# HV_Module.net
KiCad netlist of a schematic drawn in Altium Designer
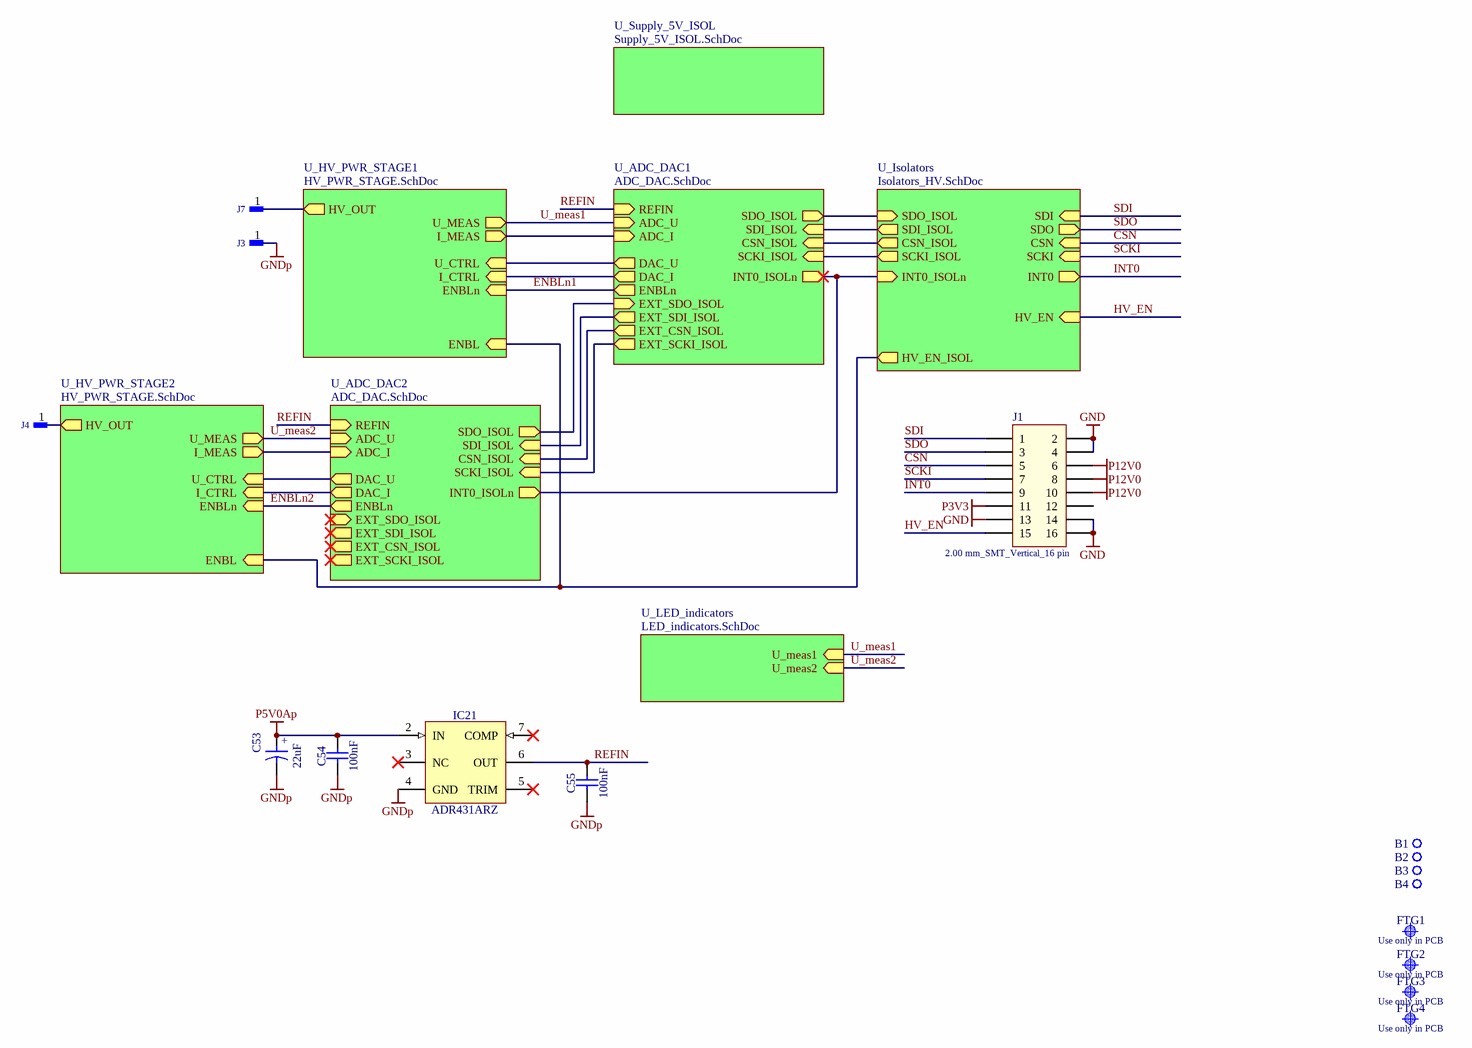
[diagram p0: HV_Module.schdoc]

(export (version "E")
  (design (tool "Eeschema 10.0.6"))
  (components
    (comp (ref "B1")
      (value "Plated Hole")
      (footprint "MTG270_500")
      (description "Single Terminal Socket")
      (fields (field (name "PART NUMBER") "PLATED_HOLE2.7_PAD5.0") (field (name "AUTHOR") "CERN DEM JMW"))
      (libsource (lib "Eletro-mechanical") (part "Single Terminal Socket"))
    )
    (comp (ref "B2")
      (value "Plated Hole")
      (footprint "MTG270_500")
      (description "Single Terminal Socket")
      (fields (field (name "PART NUMBER") "PLATED_HOLE2.7_PAD5.0") (field (name "AUTHOR") "CERN DEM JMW"))
      (libsource (lib "Eletro-mechanical") (part "Single Terminal Socket"))
    )
    (comp (ref "B3")
      (value "Plated Hole")
      (footprint "MTG270_500")
      (description "Single Terminal Socket")
      (fields (field (name "PART NUMBER") "PLATED_HOLE2.7_PAD5.0") (field (name "AUTHOR") "CERN DEM JMW"))
      (libsource (lib "Eletro-mechanical") (part "Single Terminal Socket"))
    )
    (comp (ref "B4")
      (value "Plated Hole")
      (footprint "MTG270_500")
      (description "Single Terminal Socket")
      (fields (field (name "PART NUMBER") "PLATED_HOLE2.7_PAD5.0") (field (name "AUTHOR") "CERN DEM JMW"))
      (libsource (lib "Eletro-mechanical") (part "Single Terminal Socket"))
    )
    (comp (ref "C53")
      (value "22uF")
      (footprint "CAPMP3528X210N")
      (description "Polarised capacitor")
      (fields
        (field (name "PART NUMBER") "CTE3528-21_22UF_20V_10%")
        (field (name "VOLTAGE") "20V")
        (field (name "AUTHOR") "CERN DEM JLC")
      )
      (libsource (lib "Capacitors") (part "Capacitor - polarized"))
    )
    (comp (ref "C54")
      (value "100nF")
      (footprint "CAPC1005X55N")
      (description "Non-polarised capacitor")
      (fields
        (field (name "PART NUMBER") "CC0402_100NF_16V_10%_X7R")
        (field (name "VOLTAGE") "16V")
        (field (name "AUTHOR") "CERN DEM JLC")
      )
      (libsource (lib "Capacitors") (part "Capacitor - non polarized"))
    )
    (comp (ref "C55")
      (value "100nF")
      (footprint "CAPC1005X55N")
      (description "Non-polarised capacitor")
      (fields
        (field (name "PART NUMBER") "CC0402_100NF_16V_10%_X7R")
        (field (name "VOLTAGE") "16V")
        (field (name "AUTHOR") "CERN DEM JLC")
      )
      (libsource (lib "Capacitors") (part "Capacitor - non polarized"))
    )
    (comp (ref "FTG1")
      (value "Use only in PCB")
      (footprint "FIDUCIAL_TOP_C100-200")
      (description "Fiducial Target")
      (fields (field (name "PART NUMBER") "FIDUCIAL_TARGET_C100-200") (field (name "AUTHOR") "CERN DEM JLC"))
      (libsource (lib "Eletro-mechanical") (part "Fiducial Target"))
    )
    (comp (ref "FTG2")
      (value "Use only in PCB")
      (footprint "FIDUCIAL_TOP_S100-200")
      (description "Fiducial Target")
      (fields (field (name "PART NUMBER") "FIDUCIAL_TARGET_S100-200") (field (name "AUTHOR") "CERN DEM JLC"))
      (libsource (lib "Eletro-mechanical") (part "Fiducial Target"))
    )
    (comp (ref "FTG3")
      (value "Use only in PCB")
      (footprint "FIDUCIAL_TOP_S100-200")
      (description "Fiducial Target")
      (fields (field (name "PART NUMBER") "FIDUCIAL_TARGET_S100-200") (field (name "AUTHOR") "CERN DEM JLC"))
      (libsource (lib "Eletro-mechanical") (part "Fiducial Target"))
    )
    (comp (ref "FTG4")
      (value "Use only in PCB")
      (footprint "FIDUCIAL_TOP_S100-200")
      (description "Fiducial Target")
      (fields (field (name "PART NUMBER") "FIDUCIAL_TARGET_S100-200") (field (name "AUTHOR") "CERN DEM JLC"))
      (libsource (lib "Eletro-mechanical") (part "Fiducial Target"))
    )
    (comp (ref "IC21")
      (value "ADR431ARZ")
      (footprint "SOIC127P600X175-8N")
      (fields (field (name "MANUFACTURER") "ANALOG DEVICES") (field (name "AUTHOR") "CERN DEM JLC"))
      (libsource (lib "ICs And Semiconductors") (part "ADR431"))
    )
    (comp (ref "J1")
      (value "2.00 mm_SMT_Vertical_16 pin")
      (footprint "62131621821")
      (description "Socket Header WR-PHD, Pitch 2.00 mm, SMT, Vertical, dual row, 16 pin")
      (fields (field (name "PART NUMBER") "62131621821") (field (name "PUBLISHER") "Wurth Elektronik"))
      (libsource (lib "ALTIUM-PHD_2_0_SMT_DUAL_SOCKET_HEADER_LOW_PROFILE_REEL_6213XX21821-rev18a") (part "62131621821"))
    )
    (comp (ref "J3")
      (value "SMD Pad")
      (footprint "R400X300")
      (description "Single SMD Pad")
      (fields (field (name "PART NUMBER") "SMD_PAD_4X3MM") (field (name "AUTHOR") "CERN DEM JLC"))
      (libsource (lib "Eletro-mechanical") (part "Single SMD Pad"))
    )
    (comp (ref "J4")
      (value "SMD Pad")
      (footprint "R400X300")
      (description "Single SMD Pad")
      (fields (field (name "PART NUMBER") "SMD_PAD_4X3MM") (field (name "AUTHOR") "CERN DEM JLC"))
      (libsource (lib "Eletro-mechanical") (part "Single SMD Pad"))
    )
    (comp (ref "J7")
      (value "SMD Pad")
      (footprint "R400X300")
      (description "Single SMD Pad")
      (fields (field (name "PART NUMBER") "SMD_PAD_4X3MM") (field (name "AUTHOR") "CERN DEM JLC"))
      (libsource (lib "Eletro-mechanical") (part "Single SMD Pad"))
    )
  )
  (nets
    (net (code "1") (name "/CSN") (class "Default")
      (node (ref "J1") (pin "5") (pinfunction "5_5") (pintype "passive"))
    )
    (net (code "16") (name "/HV_EN") (class "Default")
      (node (ref "J1") (pin "15") (pinfunction "15_15") (pintype "passive"))
    )
    (net (code "18") (name "/HV_OUT") (class "Default")
      (node (ref "J7") (pin "1") (pinfunction "1_1") (pintype "bidirectional"))
    )
    (net (code "19") (name "/HV_OUT_1") (class "Default")
      (node (ref "J4") (pin "1") (pinfunction "1_1") (pintype "bidirectional"))
    )
    (net (code "20") (name "/INT0") (class "Default")
      (node (ref "J1") (pin "9") (pinfunction "9_9") (pintype "passive"))
    )
    (net (code "24") (name "/REFIN") (class "Default")
      (node (ref "C55") (pin "2") (pinfunction "2_2") (pintype "passive"))
      (node (ref "IC21") (pin "6") (pinfunction "OUT_6") (pintype "power_in"))
    )
    (net (code "25") (name "/SCKI") (class "Default")
      (node (ref "J1") (pin "7") (pinfunction "7_7") (pintype "passive"))
    )
    (net (code "27") (name "/SDI") (class "Default")
      (node (ref "J1") (pin "1") (pinfunction "1_1") (pintype "passive"))
    )
    (net (code "29") (name "/SDO") (class "Default")
      (node (ref "J1") (pin "3") (pinfunction "3_3") (pintype "passive"))
    )
    (net (code "34") (name "GND") (class "Default")
      (node (ref "J1") (pin "13") (pinfunction "13_13") (pintype "passive"))
      (node (ref "J1") (pin "14") (pinfunction "14_14") (pintype "passive"))
      (node (ref "J1") (pin "16") (pinfunction "16_16") (pintype "passive"))
      (node (ref "J1") (pin "2") (pinfunction "2_2") (pintype "passive"))
      (node (ref "J1") (pin "4") (pinfunction "4_4") (pintype "passive"))
    )
    (net (code "35") (name "GNDp") (class "Default")
      (node (ref "C53") (pin "2") (pinfunction "2_2") (pintype "passive"))
      (node (ref "C54") (pin "1") (pinfunction "1_1") (pintype "passive"))
      (node (ref "C55") (pin "1") (pinfunction "1_1") (pintype "passive"))
      (node (ref "IC21") (pin "4") (pinfunction "GND_4") (pintype "power_in"))
      (node (ref "J3") (pin "1") (pinfunction "1_1") (pintype "bidirectional"))
    )
    (net (code "36") (name "P3V3") (class "Default")
      (node (ref "J1") (pin "11") (pinfunction "11_11") (pintype "passive"))
    )
    (net (code "37") (name "P5V0Ap") (class "Default")
      (node (ref "C53") (pin "1") (pinfunction "1_1") (pintype "passive"))
      (node (ref "C54") (pin "2") (pinfunction "2_2") (pintype "passive"))
      (node (ref "IC21") (pin "2") (pinfunction "IN_2") (pintype "input"))
    )
    (net (code "38") (name "P12V0") (class "Default")
      (node (ref "J1") (pin "10") (pinfunction "10_10") (pintype "passive"))
      (node (ref "J1") (pin "6") (pinfunction "6_6") (pintype "passive"))
      (node (ref "J1") (pin "8") (pinfunction "8_8") (pintype "passive"))
    )
    (net (code "39") (name "unconnected-(B1-Pad1)") (class "Default")
      (node (ref "B1") (pin "1") (pinfunction "1_1") (pintype "bidirectional"))
    )
    (net (code "40") (name "unconnected-(B2-Pad1)") (class "Default")
      (node (ref "B2") (pin "1") (pinfunction "1_1") (pintype "bidirectional"))
    )
    (net (code "41") (name "unconnected-(B3-Pad1)") (class "Default")
      (node (ref "B3") (pin "1") (pinfunction "1_1") (pintype "bidirectional"))
    )
    (net (code "42") (name "unconnected-(B4-Pad1)") (class "Default")
      (node (ref "B4") (pin "1") (pinfunction "1_1") (pintype "bidirectional"))
    )
    (net (code "43") (name "unconnected-(IC21-COMP-Pad7)") (class "Default")
      (node (ref "IC21") (pin "7") (pinfunction "COMP_7") (pintype "input+no_connect"))
    )
    (net (code "44") (name "unconnected-(IC21-NC-Pad3)") (class "Default")
      (node (ref "IC21") (pin "3") (pinfunction "NC_3") (pintype "passive+no_connect"))
    )
    (net (code "45") (name "unconnected-(IC21-TRIM-Pad5)") (class "Default")
      (node (ref "IC21") (pin "5") (pinfunction "TRIM_5") (pintype "passive+no_connect"))
    )
    (net (code "46") (name "unconnected-(J1-Pad12)") (class "Default")
      (node (ref "J1") (pin "12") (pinfunction "12_12") (pintype "passive"))
    )
  )
)
